# tutorial4.net
KiCad netlist of a schematic drawn in EAGLE
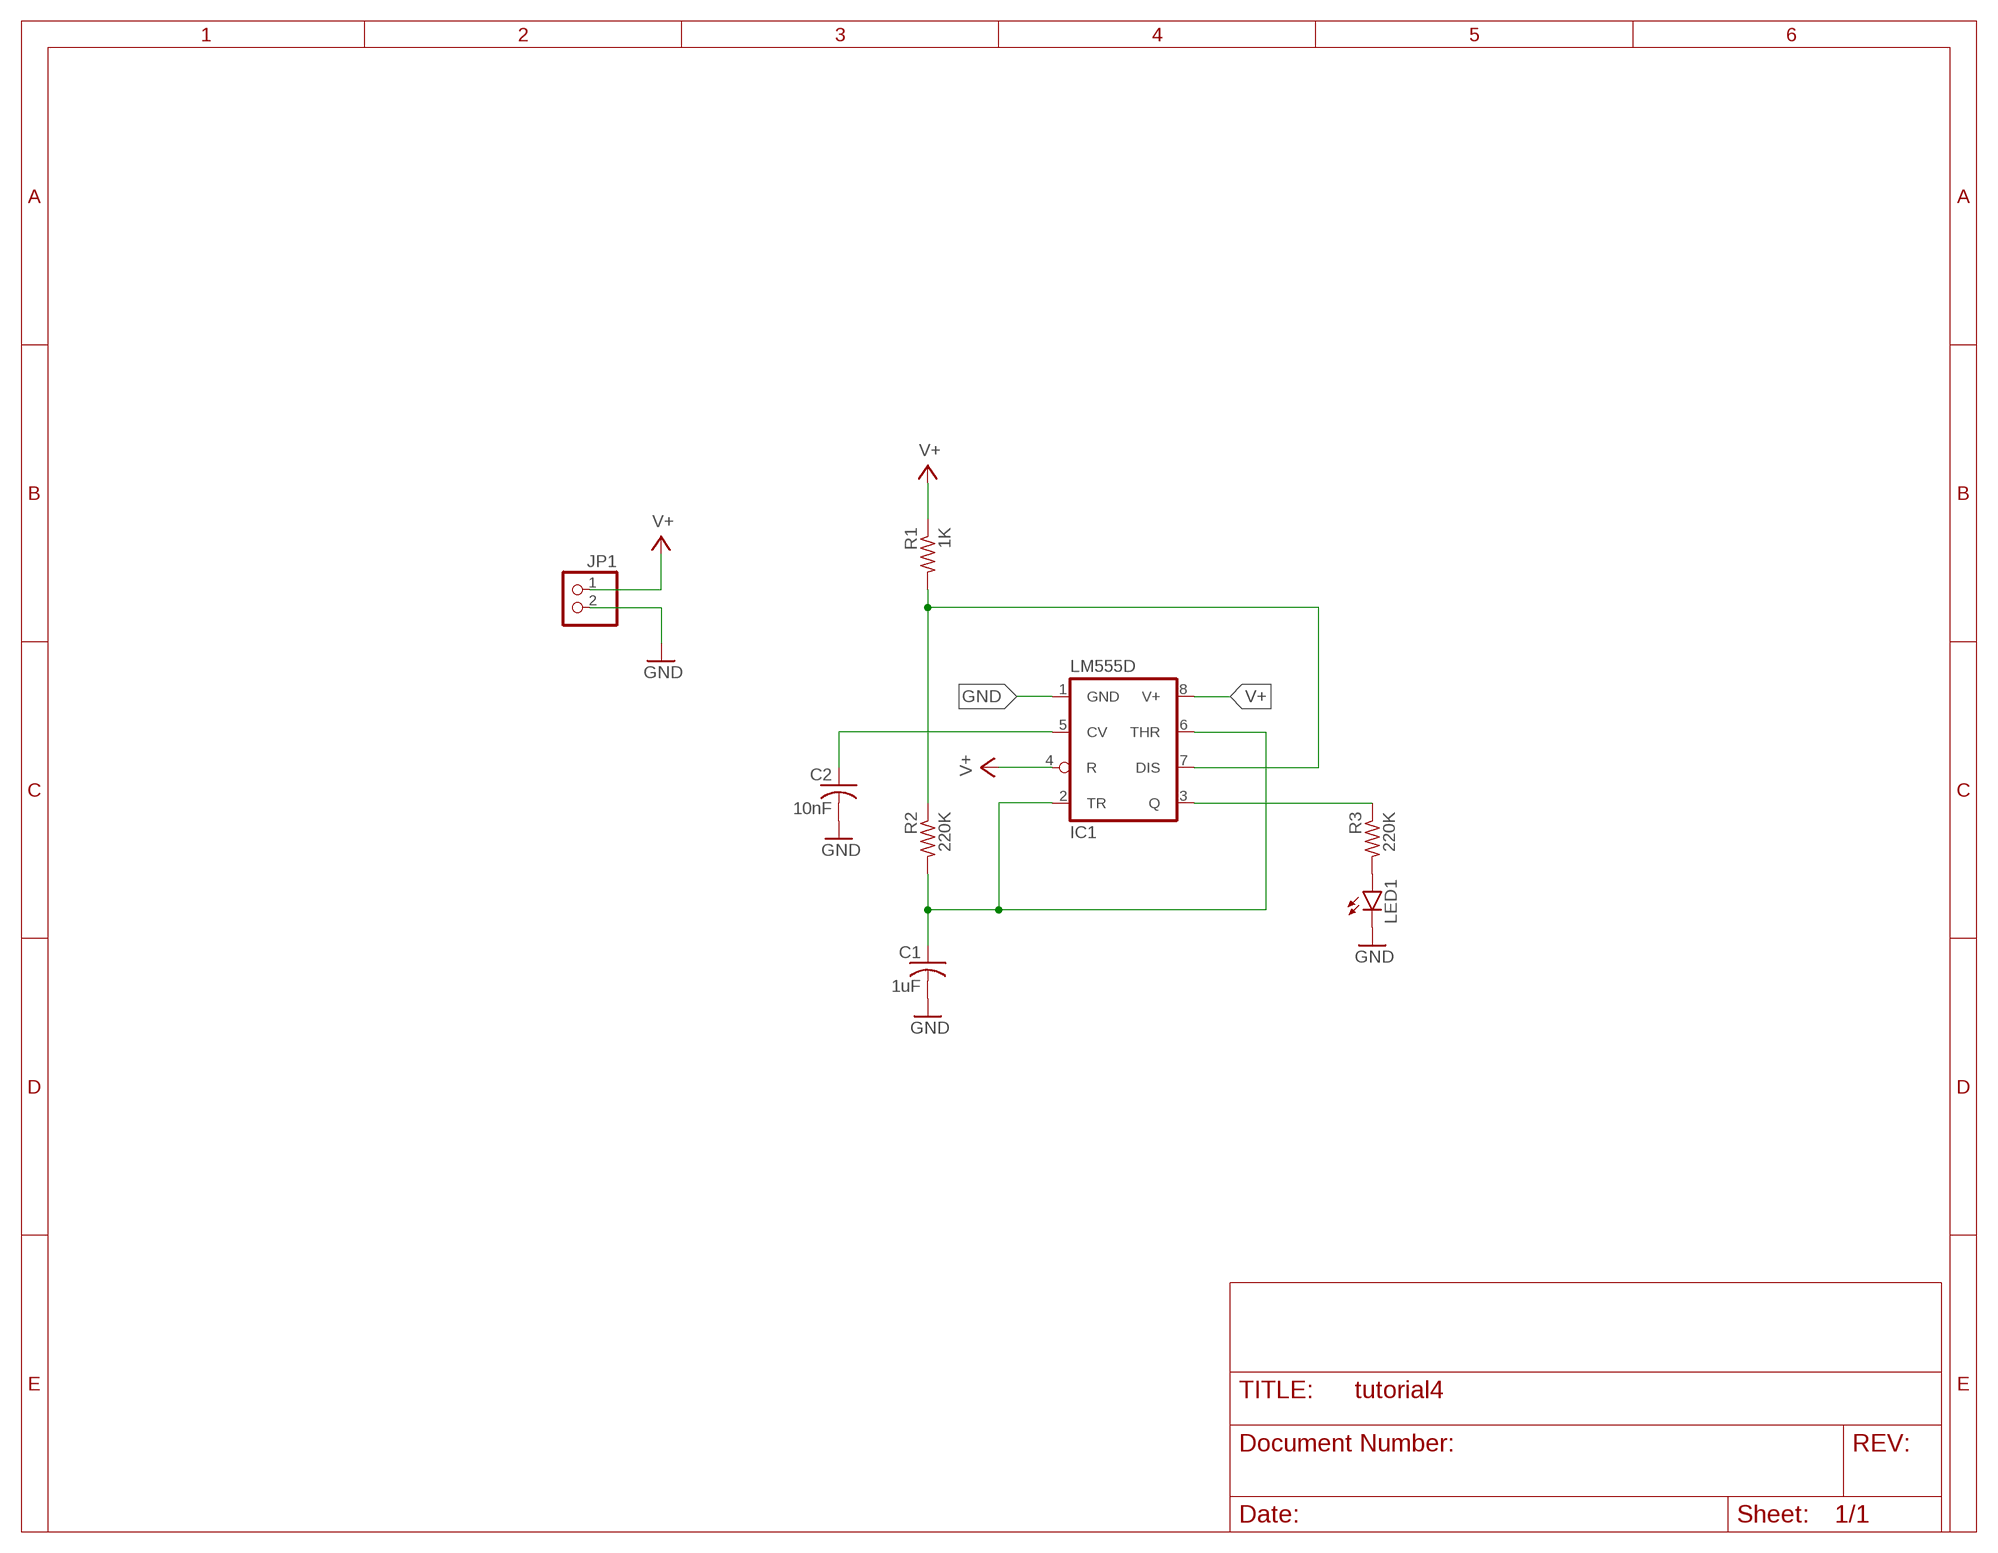
[diagram p0: schematic, sheet 1]

(export (version "E")
  (design (tool "Eeschema 10.0.6"))
  (components
    (comp (ref "C1")
      (value "1uF")
      (footprint "eagle-import:C0603")
      (libsource (lib "eagle-import") (part "C-USC0603"))
    )
    (comp (ref "C2")
      (value "10nF")
      (footprint "eagle-import:C0603")
      (libsource (lib "eagle-import") (part "C-USC0603"))
    )
    (comp (ref "IC1")
      (value "LM555D")
      (footprint "eagle-import:SO08")
      (libsource (lib "eagle-import") (part "555DLM"))
    )
    (comp (ref "JP1")
      (value "PINHD-1X2")
      (footprint "eagle-import:1X02")
      (libsource (lib "eagle-import") (part "PINHD-1X2"))
    )
    (comp (ref "LED1")
      (value "LED5MM")
      (footprint "eagle-import:LED5MM")
      (libsource (lib "eagle-import") (part "LED5MM"))
    )
    (comp (ref "R1")
      (value "1K")
      (footprint "eagle-import:R0603")
      (libsource (lib "eagle-import") (part "R-US_R0603"))
    )
    (comp (ref "R2")
      (value "220K")
      (footprint "eagle-import:R0603")
      (libsource (lib "eagle-import") (part "R-US_R0603"))
    )
    (comp (ref "R3")
      (value "220K")
      (footprint "eagle-import:R0603")
      (libsource (lib "eagle-import") (part "R-US_R0603"))
    )
  )
  (nets
    (net (code "1") (name "GND") (class "Default")
      (node (ref "C1") (pin "2") (pinfunction "2_2") (pintype "passive"))
      (node (ref "C2") (pin "2") (pinfunction "2_2") (pintype "passive"))
      (node (ref "IC1") (pin "1") (pinfunction "GND_1") (pintype "power_in"))
      (node (ref "JP1") (pin "2") (pinfunction "2_2") (pintype "passive"))
      (node (ref "LED1") (pin "K") (pinfunction "C_K") (pintype "passive"))
    )
    (net (code "2") (name "Net-(IC1-CV)") (class "Default")
      (node (ref "C2") (pin "1") (pinfunction "1_1") (pintype "passive"))
      (node (ref "IC1") (pin "5") (pinfunction "CV_5") (pintype "input"))
    )
    (net (code "3") (name "Net-(IC1-DIS)") (class "Default")
      (node (ref "IC1") (pin "7") (pinfunction "DIS_7") (pintype "input"))
      (node (ref "R1") (pin "2") (pinfunction "2_2") (pintype "passive"))
      (node (ref "R2") (pin "1") (pinfunction "1_1") (pintype "passive"))
    )
    (net (code "4") (name "Net-(IC1-Q)") (class "Default")
      (node (ref "IC1") (pin "3") (pinfunction "Q_3") (pintype "output"))
      (node (ref "R3") (pin "1") (pinfunction "1_1") (pintype "passive"))
    )
    (net (code "5") (name "Net-(IC1-THR)") (class "Default")
      (node (ref "C1") (pin "1") (pinfunction "1_1") (pintype "passive"))
      (node (ref "IC1") (pin "2") (pinfunction "TR_2") (pintype "input"))
      (node (ref "IC1") (pin "6") (pinfunction "THR_6") (pintype "input"))
      (node (ref "R2") (pin "2") (pinfunction "2_2") (pintype "passive"))
    )
    (net (code "6") (name "Net-(LED1-PadA)") (class "Default")
      (node (ref "LED1") (pin "A") (pinfunction "A_A") (pintype "passive"))
      (node (ref "R3") (pin "2") (pinfunction "2_2") (pintype "passive"))
    )
    (net (code "7") (name "V+") (class "Default")
      (node (ref "IC1") (pin "4") (pinfunction "R_4") (pintype "input"))
      (node (ref "IC1") (pin "8") (pinfunction "V+_8") (pintype "power_in"))
      (node (ref "JP1") (pin "1") (pinfunction "1_1") (pintype "passive"))
      (node (ref "R1") (pin "1") (pinfunction "1_1") (pintype "passive"))
    )
  )
)
